# drive.net
KiCad netlist of a schematic drawn in EAGLE
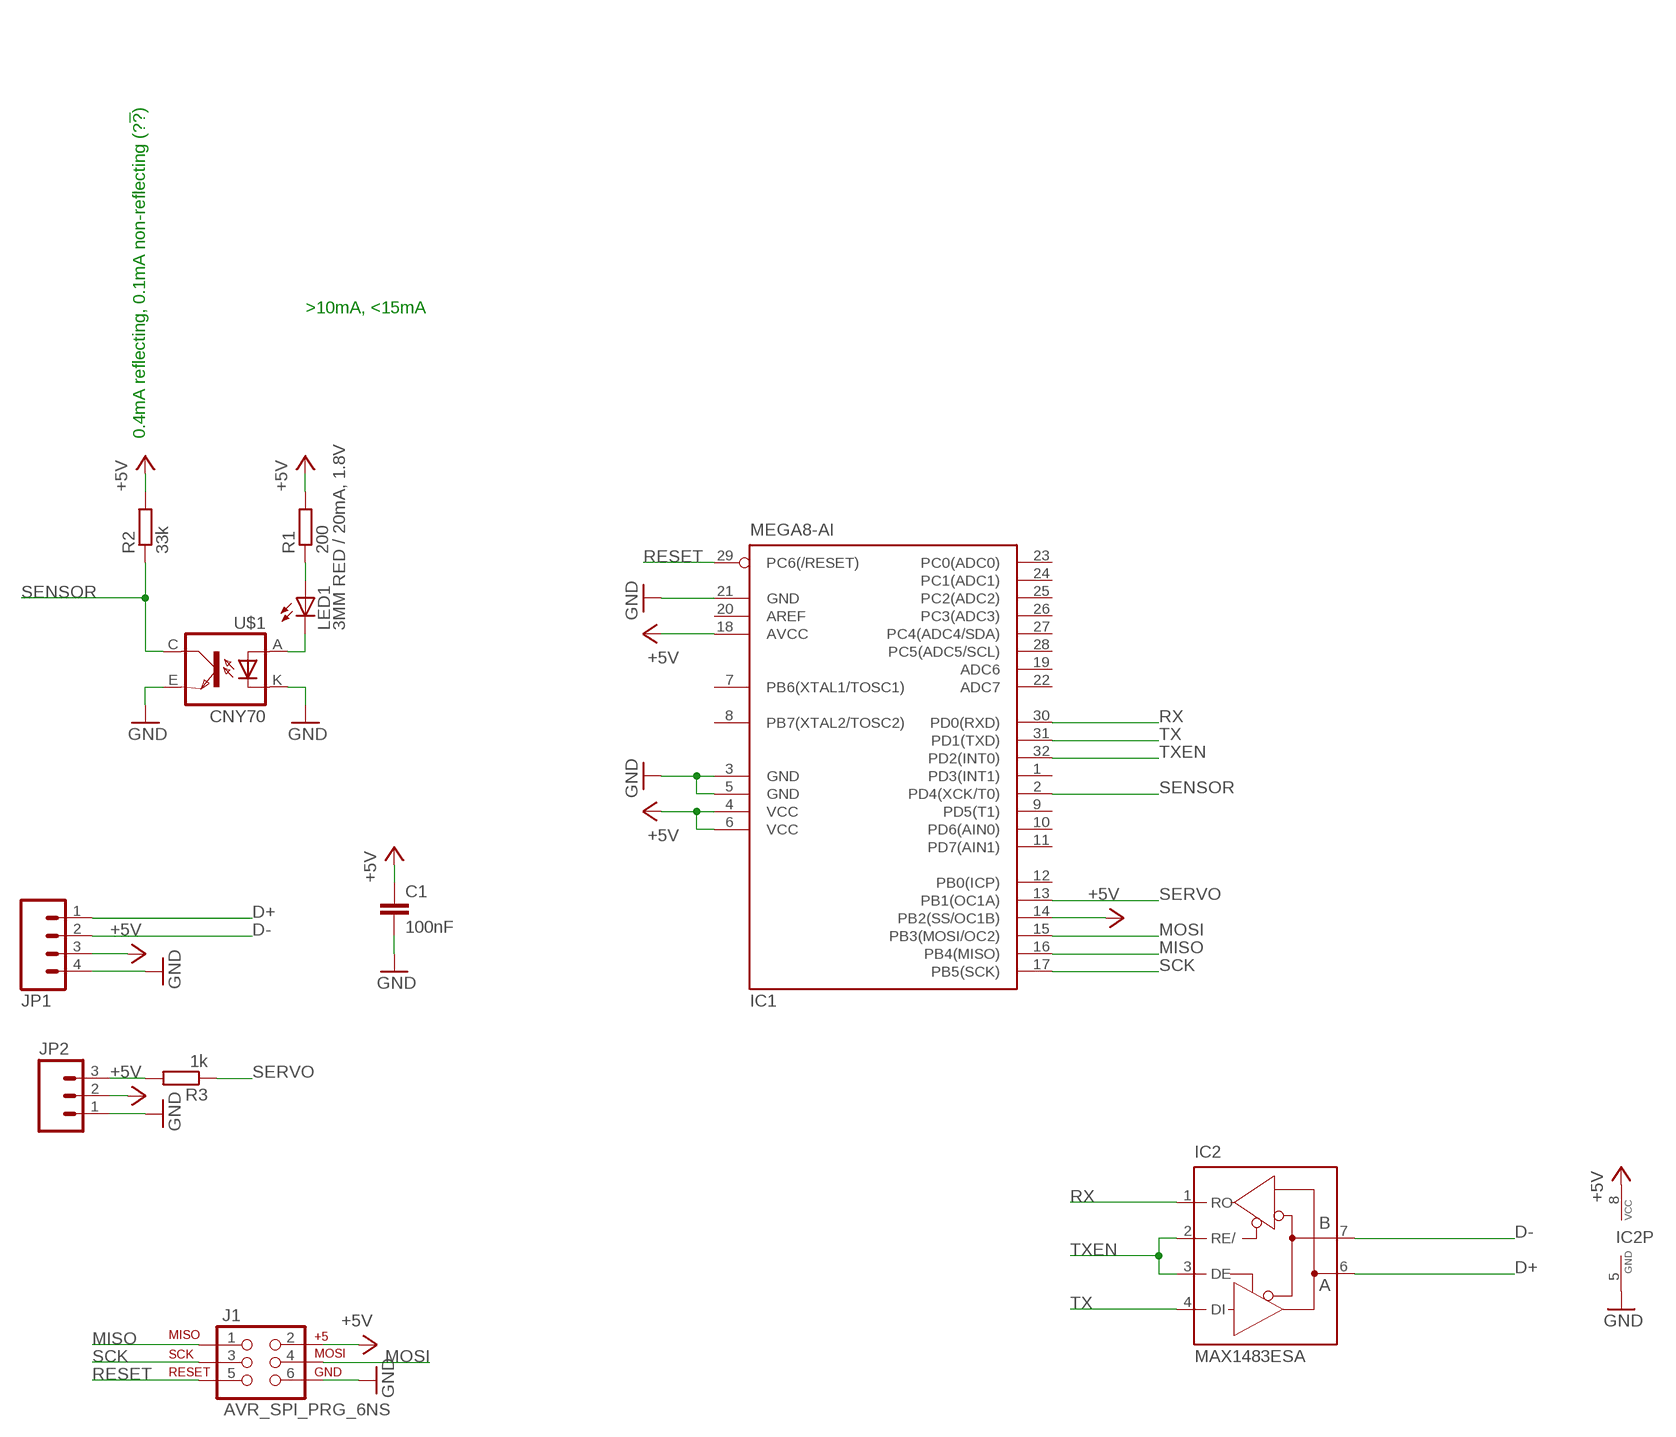
[diagram p0: schematic, sheet 1]

(export (version "E")
  (design (tool "Eeschema 10.0.6"))
  (components
    (comp (ref "C1")
      (value "100nF")
      (footprint "eagle-import:C0805")
      (libsource (lib "eagle-import") (part "C-EUC0805"))
    )
    (comp (ref "IC1")
      (value "MEGA8-AI")
      (footprint "eagle-import:TQFP32-08")
      (fields (field (name "MPN") "ATMEGA8-16AU"))
      (libsource (lib "eagle-import") (part "MEGA8-AI"))
    )
    (comp (ref "IC2")
      (value "MAX1483ESA")
      (footprint "eagle-import:SO08")
      (fields (field (name "MF") "MAXIM") (field (name "MPN") "MAX481CSA"))
      (libsource (lib "eagle-import") (part "MAX481CSA"))
    )
    (comp (ref "J1")
      (value "AVR_SPI_PRG_6NS")
      (footprint "eagle-import:2X3-NS")
      (libsource (lib "eagle-import") (part "AVR_SPI_PRG_6NS"))
    )
    (comp (ref "JP1")
      (value "M04POLAR")
      (footprint "eagle-import:MOLEX-1X4")
      (libsource (lib "eagle-import") (part "M04POLAR"))
    )
    (comp (ref "JP2")
      (value "M03PTH")
      (footprint "eagle-import:1X03")
      (libsource (lib "eagle-import") (part "M03PTH"))
    )
    (comp (ref "LED1")
      (value "3MM RED / 20mA, 1.8V")
      (footprint "eagle-import:LED3MM")
      (libsource (lib "eagle-import") (part "LED3MM"))
    )
    (comp (ref "R1")
      (value "200")
      (footprint "eagle-import:R0805")
      (libsource (lib "eagle-import") (part "R-EU_R0805"))
    )
    (comp (ref "R2")
      (value "33k")
      (footprint "eagle-import:R0805")
      (libsource (lib "eagle-import") (part "R-EU_R0805"))
    )
    (comp (ref "R3")
      (value "1k")
      (footprint "eagle-import:R0805")
      (libsource (lib "eagle-import") (part "R-EU_R0805"))
    )
    (comp (ref "U$1")
      (value "CNY70")
      (footprint "eagle-import:4")
      (libsource (lib "eagle-import") (part "CNY70"))
    )
  )
  (nets
    (net (code "1") (name "+5V") (class "Default")
      (node (ref "C1") (pin "1") (pinfunction "1_1") (pintype "passive"))
      (node (ref "IC1") (pin "14") (pinfunction "PB2(SS/OC1B)_14") (pintype "bidirectional"))
      (node (ref "IC1") (pin "18") (pinfunction "AVCC_18") (pintype "power_in"))
      (node (ref "IC1") (pin "4") (pinfunction "VCC_4") (pintype "power_in"))
      (node (ref "IC1") (pin "6") (pinfunction "VCC_6") (pintype "power_in"))
      (node (ref "IC2") (pin "8") (pinfunction "VCC_8") (pintype "power_in"))
      (node (ref "J1") (pin "2") (pinfunction "2_2") (pintype "passive"))
      (node (ref "JP1") (pin "3") (pinfunction "3_3") (pintype "passive"))
      (node (ref "JP2") (pin "2") (pinfunction "2_2") (pintype "passive"))
      (node (ref "R1") (pin "2") (pinfunction "2_2") (pintype "passive"))
      (node (ref "R2") (pin "2") (pinfunction "2_2") (pintype "passive"))
    )
    (net (code "2") (name "/D+") (class "Default")
      (node (ref "IC2") (pin "6") (pinfunction "A_6") (pintype "passive"))
      (node (ref "JP1") (pin "1") (pinfunction "1_1") (pintype "passive"))
    )
    (net (code "3") (name "/D-") (class "Default")
      (node (ref "IC2") (pin "7") (pinfunction "B_7") (pintype "passive"))
      (node (ref "JP1") (pin "2") (pinfunction "2_2") (pintype "passive"))
    )
    (net (code "4") (name "/MISO") (class "Default")
      (node (ref "IC1") (pin "16") (pinfunction "PB4(MISO)_16") (pintype "bidirectional"))
      (node (ref "J1") (pin "1") (pinfunction "1_1") (pintype "passive"))
    )
    (net (code "5") (name "/MOSI") (class "Default")
      (node (ref "IC1") (pin "15") (pinfunction "PB3(MOSI/OC2)_15") (pintype "bidirectional"))
      (node (ref "J1") (pin "4") (pinfunction "4_4") (pintype "passive"))
    )
    (net (code "6") (name "/RESET") (class "Default")
      (node (ref "IC1") (pin "29") (pinfunction "PC6(/RESET)_29") (pintype "bidirectional"))
      (node (ref "J1") (pin "5") (pinfunction "5_5") (pintype "passive"))
    )
    (net (code "7") (name "/RX") (class "Default")
      (node (ref "IC1") (pin "30") (pinfunction "PD0(RXD)_30") (pintype "bidirectional"))
      (node (ref "IC2") (pin "1") (pinfunction "RO_1") (pintype "output"))
    )
    (net (code "8") (name "/SCK") (class "Default")
      (node (ref "IC1") (pin "17") (pinfunction "PB5(SCK)_17") (pintype "bidirectional"))
      (node (ref "J1") (pin "3") (pinfunction "3_3") (pintype "passive"))
    )
    (net (code "9") (name "/SENSOR") (class "Default")
      (node (ref "IC1") (pin "2") (pinfunction "PD4(XCK/T0)_2") (pintype "bidirectional"))
      (node (ref "R2") (pin "1") (pinfunction "1_1") (pintype "passive"))
      (node (ref "U$1") (pin "C") (pinfunction "COL_C") (pintype "passive"))
    )
    (net (code "10") (name "/SERVO") (class "Default")
      (node (ref "IC1") (pin "13") (pinfunction "PB1(OC1A)_13") (pintype "bidirectional"))
      (node (ref "R3") (pin "1") (pinfunction "1_1") (pintype "passive"))
    )
    (net (code "11") (name "/TX") (class "Default")
      (node (ref "IC1") (pin "31") (pinfunction "PD1(TXD)_31") (pintype "bidirectional"))
      (node (ref "IC2") (pin "4") (pinfunction "DI_4") (pintype "input"))
    )
    (net (code "12") (name "/TXEN") (class "Default")
      (node (ref "IC1") (pin "32") (pinfunction "PD2(INT0)_32") (pintype "bidirectional"))
      (node (ref "IC2") (pin "2") (pinfunction "RE/_2") (pintype "input"))
      (node (ref "IC2") (pin "3") (pinfunction "DE_3") (pintype "input"))
    )
    (net (code "13") (name "GND") (class "Default")
      (node (ref "C1") (pin "2") (pinfunction "2_2") (pintype "passive"))
      (node (ref "IC1") (pin "21") (pinfunction "GND_21") (pintype "power_in"))
      (node (ref "IC1") (pin "3") (pinfunction "GND_3") (pintype "power_in"))
      (node (ref "IC1") (pin "5") (pinfunction "GND_5") (pintype "power_in"))
      (node (ref "IC2") (pin "5") (pinfunction "GND_5") (pintype "power_in"))
      (node (ref "J1") (pin "6") (pinfunction "6_6") (pintype "passive"))
      (node (ref "JP1") (pin "4") (pinfunction "4_4") (pintype "passive"))
      (node (ref "JP2") (pin "1") (pinfunction "1_1") (pintype "passive"))
      (node (ref "U$1") (pin "E") (pinfunction "EMI_E") (pintype "passive"))
      (node (ref "U$1") (pin "K") (pinfunction "C_K") (pintype "passive"))
    )
    (net (code "14") (name "Net-(JP2-Pad3)") (class "Default")
      (node (ref "JP2") (pin "3") (pinfunction "3_3") (pintype "passive"))
      (node (ref "R3") (pin "2") (pinfunction "2_2") (pintype "passive"))
    )
    (net (code "15") (name "Net-(LED1-C)") (class "Default")
      (node (ref "LED1") (pin "K") (pinfunction "C_K") (pintype "passive"))
      (node (ref "U$1") (pin "A") (pinfunction "A_A") (pintype "passive"))
    )
    (net (code "16") (name "Net-(LED1-PadA)") (class "Default")
      (node (ref "LED1") (pin "A") (pinfunction "A_A") (pintype "passive"))
      (node (ref "R1") (pin "1") (pinfunction "1_1") (pintype "passive"))
    )
    (net (code "17") (name "unconnected-(IC1-ADC6-Pad19)") (class "Default")
      (node (ref "IC1") (pin "19") (pinfunction "ADC6_19") (pintype "bidirectional"))
    )
    (net (code "18") (name "unconnected-(IC1-ADC7-Pad22)") (class "Default")
      (node (ref "IC1") (pin "22") (pinfunction "ADC7_22") (pintype "bidirectional"))
    )
    (net (code "19") (name "unconnected-(IC1-AREF-Pad20)") (class "Default")
      (node (ref "IC1") (pin "20") (pinfunction "AREF_20") (pintype "passive"))
    )
    (net (code "20") (name "unconnected-(IC1-PB0(ICP)-Pad12)") (class "Default")
      (node (ref "IC1") (pin "12") (pinfunction "PB0(ICP)_12") (pintype "bidirectional"))
    )
    (net (code "21") (name "unconnected-(IC1-PB6(XTAL1{slash}TOSC1)-Pad7)") (class "Default")
      (node (ref "IC1") (pin "7") (pinfunction "PB6(XTAL1/TOSC1)_7") (pintype "bidirectional"))
    )
    (net (code "22") (name "unconnected-(IC1-PB7(XTAL2{slash}TOSC2)-Pad8)") (class "Default")
      (node (ref "IC1") (pin "8") (pinfunction "PB7(XTAL2/TOSC2)_8") (pintype "bidirectional"))
    )
    (net (code "23") (name "unconnected-(IC1-PC0(ADC0)-Pad23)") (class "Default")
      (node (ref "IC1") (pin "23") (pinfunction "PC0(ADC0)_23") (pintype "bidirectional"))
    )
    (net (code "24") (name "unconnected-(IC1-PC1(ADC1)-Pad24)") (class "Default")
      (node (ref "IC1") (pin "24") (pinfunction "PC1(ADC1)_24") (pintype "bidirectional"))
    )
    (net (code "25") (name "unconnected-(IC1-PC2(ADC2)-Pad25)") (class "Default")
      (node (ref "IC1") (pin "25") (pinfunction "PC2(ADC2)_25") (pintype "bidirectional"))
    )
    (net (code "26") (name "unconnected-(IC1-PC3(ADC3)-Pad26)") (class "Default")
      (node (ref "IC1") (pin "26") (pinfunction "PC3(ADC3)_26") (pintype "bidirectional"))
    )
    (net (code "27") (name "unconnected-(IC1-PC4(ADC4{slash}SDA)-Pad27)") (class "Default")
      (node (ref "IC1") (pin "27") (pinfunction "PC4(ADC4/SDA)_27") (pintype "bidirectional"))
    )
    (net (code "28") (name "unconnected-(IC1-PC5(ADC5{slash}SCL)-Pad28)") (class "Default")
      (node (ref "IC1") (pin "28") (pinfunction "PC5(ADC5/SCL)_28") (pintype "bidirectional"))
    )
    (net (code "29") (name "unconnected-(IC1-PD3(INT1)-Pad1)") (class "Default")
      (node (ref "IC1") (pin "1") (pinfunction "PD3(INT1)_1") (pintype "bidirectional"))
    )
    (net (code "30") (name "unconnected-(IC1-PD5(T1)-Pad9)") (class "Default")
      (node (ref "IC1") (pin "9") (pinfunction "PD5(T1)_9") (pintype "bidirectional"))
    )
    (net (code "31") (name "unconnected-(IC1-PD6(AIN0)-Pad10)") (class "Default")
      (node (ref "IC1") (pin "10") (pinfunction "PD6(AIN0)_10") (pintype "bidirectional"))
    )
    (net (code "32") (name "unconnected-(IC1-PD7(AIN1)-Pad11)") (class "Default")
      (node (ref "IC1") (pin "11") (pinfunction "PD7(AIN1)_11") (pintype "bidirectional"))
    )
  )
)
